# BradBoxV4.net
KiCad netlist of a schematic drawn in EAGLE
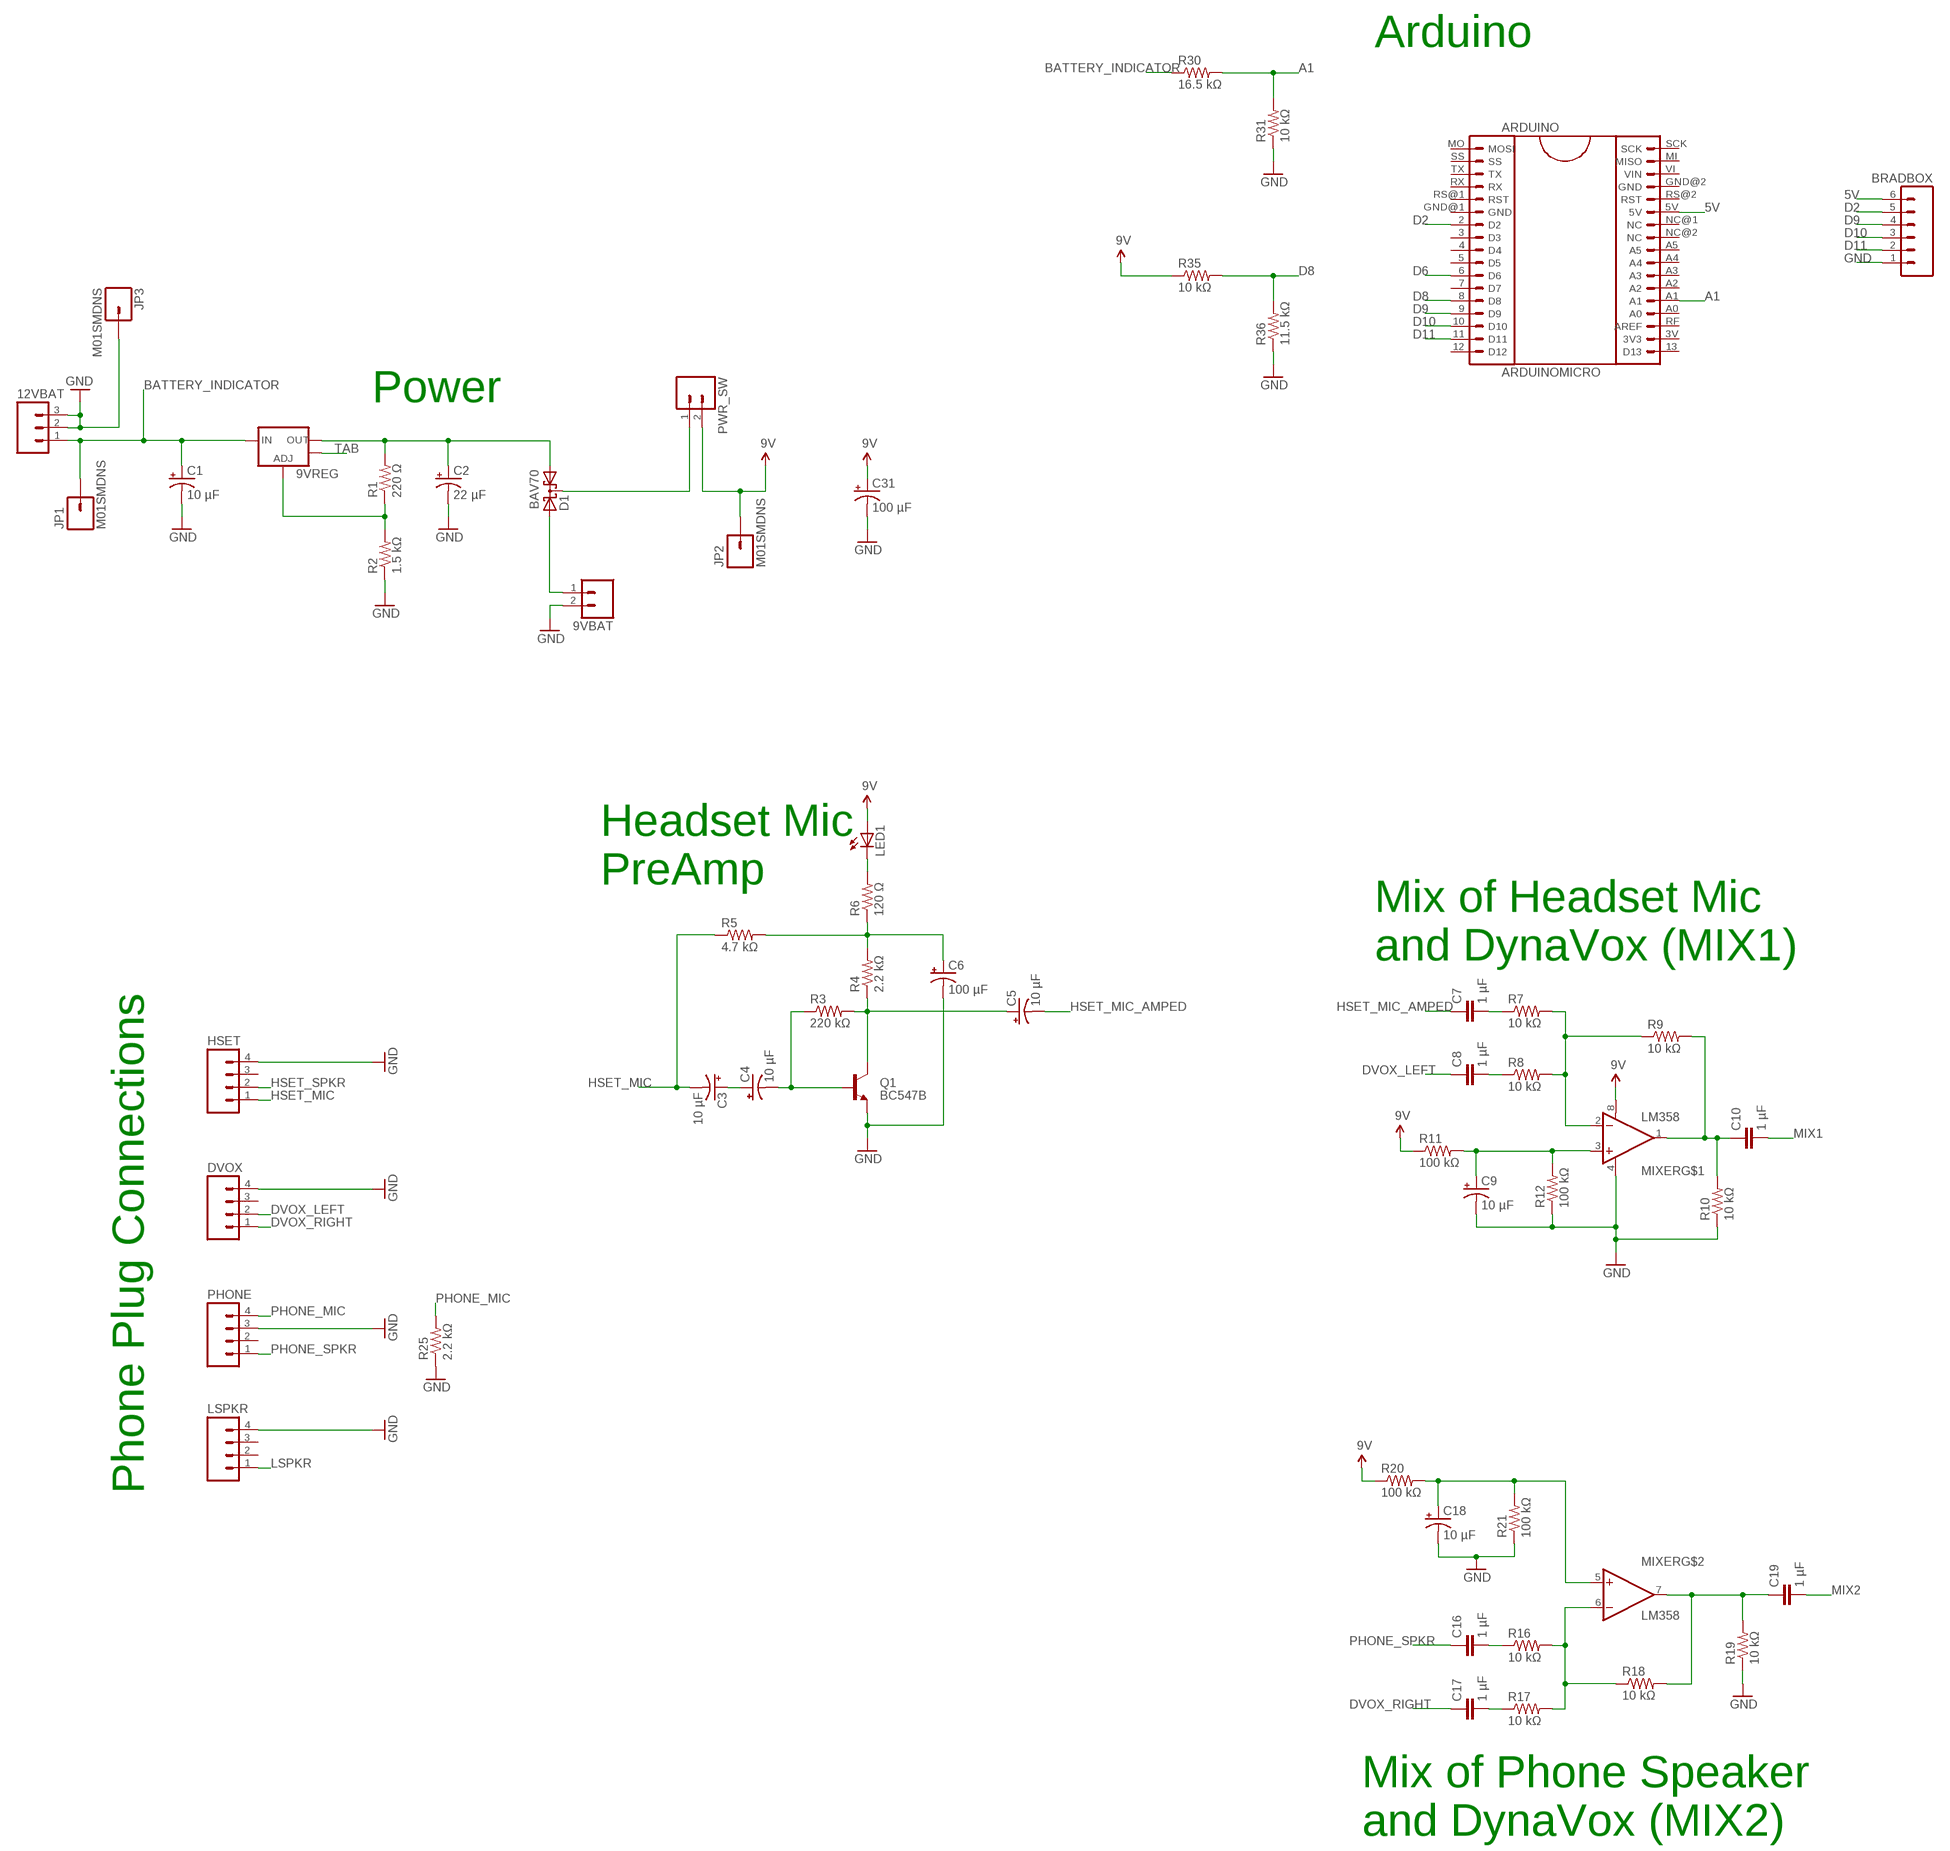
[diagram p0: schematic, sheet 1, part 1 of 2]
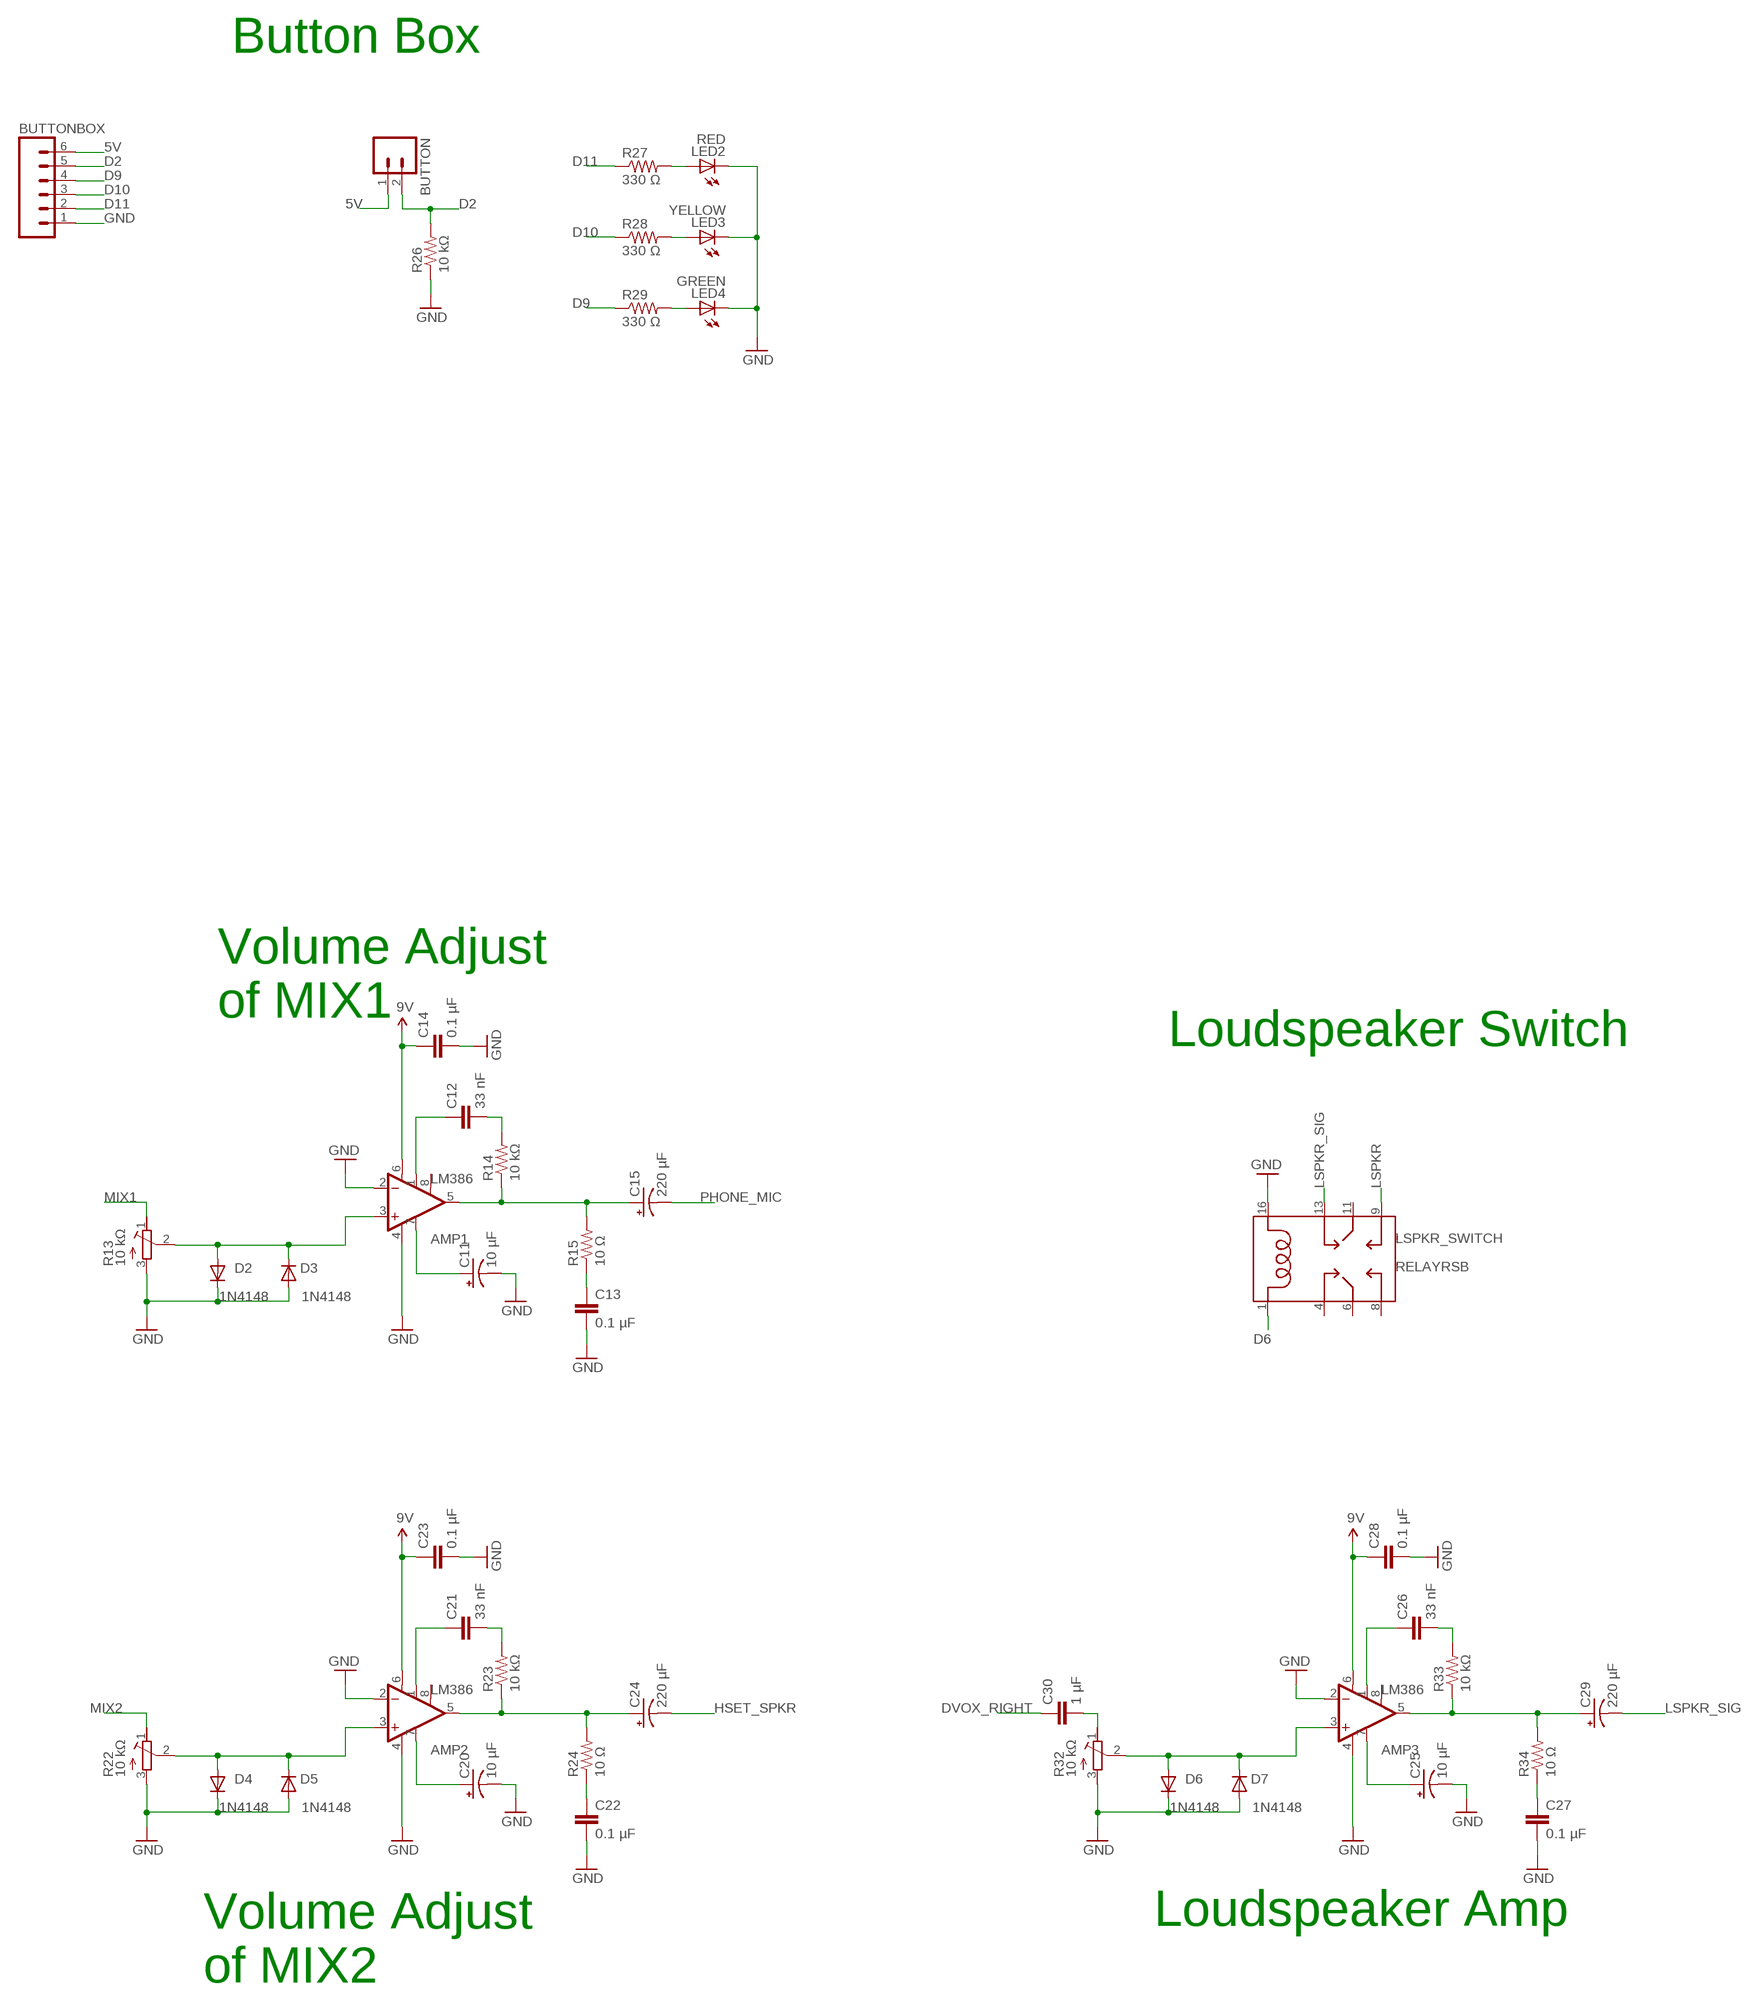
[diagram p1: schematic, sheet 1, part 2 of 2]

(export (version "E")
  (design (tool "Eeschema 10.0.6"))
  (components
    (comp (ref "9VBAT")
      (value "M02POLAR")
      (footprint "eagle-import:MOLEX-1X2")
      (libsource (lib "eagle-import") (part "M02POLAR"))
    )
    (comp (ref "9VREG")
      (value "V_REG_LM1117SOT223")
      (footprint "eagle-import:SOT223")
      (libsource (lib "eagle-import") (part "V_REG_LM1117SOT223"))
    )
    (comp (ref "12VBAT")
      (value "M03POLAR")
      (footprint "eagle-import:MOLEX-1X3")
      (libsource (lib "eagle-import") (part "M03POLAR"))
    )
    (comp (ref "AMP1")
      (value "LM386")
      (footprint "eagle-import:DIP08")
      (libsource (lib "eagle-import") (part "LM386"))
    )
    (comp (ref "AMP2")
      (value "LM386")
      (footprint "eagle-import:DIP08")
      (libsource (lib "eagle-import") (part "LM386"))
    )
    (comp (ref "AMP3")
      (value "LM386")
      (footprint "eagle-import:DIP08")
      (libsource (lib "eagle-import") (part "LM386"))
    )
    (comp (ref "ARDUINO")
      (value "ARDUINOMICRO")
      (footprint "eagle-import:ARDUINO_MICRO")
      (libsource (lib "eagle-import") (part "ARDUINOMICRO"))
    )
    (comp (ref "BRADBOX")
      (value "M06POLAR")
      (footprint "eagle-import:MOLEX-1X6")
      (libsource (lib "eagle-import") (part "M06POLAR"))
    )
    (comp (ref "BUTTON")
      (value "M02POLAR")
      (footprint "eagle-import:MOLEX-1X2")
      (libsource (lib "eagle-import") (part "M02POLAR"))
    )
    (comp (ref "BUTTONBOX")
      (value "M06POLAR")
      (footprint "eagle-import:MOLEX-1X6")
      (libsource (lib "eagle-import") (part "M06POLAR"))
    )
    (comp (ref "C1")
      (value "10 µF")
      (footprint "eagle-import:0603-CAP-POL")
      (libsource (lib "eagle-import") (part "CAP_POL0603-POL"))
    )
    (comp (ref "C2")
      (value "22 µF")
      (footprint "eagle-import:0603-CAP-POL")
      (libsource (lib "eagle-import") (part "CAP_POL0603-POL"))
    )
    (comp (ref "C3")
      (value "10 µF")
      (footprint "eagle-import:0603-CAP-POL")
      (libsource (lib "eagle-import") (part "CAP_POL0603-POL"))
    )
    (comp (ref "C4")
      (value "10 µF")
      (footprint "eagle-import:0603-CAP-POL")
      (libsource (lib "eagle-import") (part "CAP_POL0603-POL"))
    )
    (comp (ref "C5")
      (value "10 µF")
      (footprint "eagle-import:0603-CAP-POL")
      (libsource (lib "eagle-import") (part "CAP_POL0603-POL"))
    )
    (comp (ref "C6")
      (value "100 µF")
      (footprint "eagle-import:CPOL-RADIAL-100UF-100V")
      (libsource (lib "eagle-import") (part "CAP_POLPTH1"))
    )
    (comp (ref "C7")
      (value "1 µF")
      (footprint "eagle-import:0603-CAP")
      (libsource (lib "eagle-import") (part "CAP0603-CAP"))
    )
    (comp (ref "C8")
      (value "1 µF")
      (footprint "eagle-import:0603-CAP")
      (libsource (lib "eagle-import") (part "CAP0603-CAP"))
    )
    (comp (ref "C9")
      (value "10 µF")
      (footprint "eagle-import:0603-CAP-POL")
      (libsource (lib "eagle-import") (part "CAP_POL0603-POL"))
    )
    (comp (ref "C10")
      (value "1 µF")
      (footprint "eagle-import:0603-CAP")
      (libsource (lib "eagle-import") (part "CAP0603-CAP"))
    )
    (comp (ref "C11")
      (value "10 µF")
      (footprint "eagle-import:0603-CAP-POL")
      (libsource (lib "eagle-import") (part "CAP_POL0603-POL"))
    )
    (comp (ref "C12")
      (value "33 nF")
      (footprint "eagle-import:0603-CAP")
      (libsource (lib "eagle-import") (part "CAP0603-CAP"))
    )
    (comp (ref "C13")
      (value "0.1 µF")
      (footprint "eagle-import:0603-CAP")
      (libsource (lib "eagle-import") (part "CAP0603-CAP"))
    )
    (comp (ref "C14")
      (value "0.1 µF")
      (footprint "eagle-import:0603-CAP")
      (libsource (lib "eagle-import") (part "CAP0603-CAP"))
    )
    (comp (ref "C15")
      (value "220 µF")
      (footprint "eagle-import:CPOL-RADIAL-220UF-100V")
      (libsource (lib "eagle-import") (part "CAP_POLPTH4"))
    )
    (comp (ref "C16")
      (value "1 µF")
      (footprint "eagle-import:0603-CAP")
      (libsource (lib "eagle-import") (part "CAP0603-CAP"))
    )
    (comp (ref "C17")
      (value "1 µF")
      (footprint "eagle-import:0603-CAP")
      (libsource (lib "eagle-import") (part "CAP0603-CAP"))
    )
    (comp (ref "C18")
      (value "10 µF")
      (footprint "eagle-import:0603-CAP-POL")
      (libsource (lib "eagle-import") (part "CAP_POL0603-POL"))
    )
    (comp (ref "C19")
      (value "1 µF")
      (footprint "eagle-import:0603-CAP")
      (libsource (lib "eagle-import") (part "CAP0603-CAP"))
    )
    (comp (ref "C20")
      (value "10 µF")
      (footprint "eagle-import:0603-CAP-POL")
      (libsource (lib "eagle-import") (part "CAP_POL0603-POL"))
    )
    (comp (ref "C21")
      (value "33 nF")
      (footprint "eagle-import:0603-CAP")
      (libsource (lib "eagle-import") (part "CAP0603-CAP"))
    )
    (comp (ref "C22")
      (value "0.1 µF")
      (footprint "eagle-import:0603-CAP")
      (libsource (lib "eagle-import") (part "CAP0603-CAP"))
    )
    (comp (ref "C23")
      (value "0.1 µF")
      (footprint "eagle-import:0603-CAP")
      (libsource (lib "eagle-import") (part "CAP0603-CAP"))
    )
    (comp (ref "C24")
      (value "220 µF")
      (footprint "eagle-import:CPOL-RADIAL-220UF-100V")
      (libsource (lib "eagle-import") (part "CAP_POLPTH4"))
    )
    (comp (ref "C25")
      (value "10 µF")
      (footprint "eagle-import:0603-CAP-POL")
      (libsource (lib "eagle-import") (part "CAP_POL0603-POL"))
    )
    (comp (ref "C26")
      (value "33 nF")
      (footprint "eagle-import:0603-CAP")
      (libsource (lib "eagle-import") (part "CAP0603-CAP"))
    )
    (comp (ref "C27")
      (value "0.1 µF")
      (footprint "eagle-import:0603-CAP")
      (libsource (lib "eagle-import") (part "CAP0603-CAP"))
    )
    (comp (ref "C28")
      (value "0.1 µF")
      (footprint "eagle-import:0603-CAP")
      (libsource (lib "eagle-import") (part "CAP0603-CAP"))
    )
    (comp (ref "C29")
      (value "220 µF")
      (footprint "eagle-import:CPOL-RADIAL-220UF-100V")
      (libsource (lib "eagle-import") (part "CAP_POLPTH4"))
    )
    (comp (ref "C30")
      (value "1 µF")
      (footprint "eagle-import:0603-CAP")
      (libsource (lib "eagle-import") (part "CAP0603-CAP"))
    )
    (comp (ref "C31")
      (value "100 µF")
      (footprint "eagle-import:CPOL-RADIAL-100UF-100V")
      (libsource (lib "eagle-import") (part "CAP_POLPTH1"))
    )
    (comp (ref "D1")
      (value "BAV70")
      (footprint "eagle-import:SOT23")
      (libsource (lib "eagle-import") (part "BAS70-05"))
    )
    (comp (ref "D2")
      (value "1N4148")
      (footprint "eagle-import:SOD523F")
      (libsource (lib "eagle-import") (part "DIODE-SOD523F"))
    )
    (comp (ref "D3")
      (value "1N4148")
      (footprint "eagle-import:SOD523F")
      (libsource (lib "eagle-import") (part "DIODE-SOD523F"))
    )
    (comp (ref "D4")
      (value "1N4148")
      (footprint "eagle-import:SOD523F")
      (libsource (lib "eagle-import") (part "DIODE-SOD523F"))
    )
    (comp (ref "D5")
      (value "1N4148")
      (footprint "eagle-import:SOD523F")
      (libsource (lib "eagle-import") (part "DIODE-SOD523F"))
    )
    (comp (ref "D6")
      (value "1N4148")
      (footprint "eagle-import:SOD523F")
      (libsource (lib "eagle-import") (part "DIODE-SOD523F"))
    )
    (comp (ref "D7")
      (value "1N4148")
      (footprint "eagle-import:SOD523F")
      (libsource (lib "eagle-import") (part "DIODE-SOD523F"))
    )
    (comp (ref "DVOX")
      (value "M04POLAR")
      (footprint "eagle-import:MOLEX-1X4")
      (libsource (lib "eagle-import") (part "M04POLAR"))
    )
    (comp (ref "HSET")
      (value "M04POLAR")
      (footprint "eagle-import:MOLEX-1X4")
      (libsource (lib "eagle-import") (part "M04POLAR"))
    )
    (comp (ref "JP1")
      (value "M01SMDNS")
      (footprint "eagle-import:1X01NS")
      (libsource (lib "eagle-import") (part "M01SMDNS"))
    )
    (comp (ref "JP2")
      (value "M01SMDNS")
      (footprint "eagle-import:1X01NS")
      (libsource (lib "eagle-import") (part "M01SMDNS"))
    )
    (comp (ref "JP3")
      (value "M01SMDNS")
      (footprint "eagle-import:1X01NS")
      (libsource (lib "eagle-import") (part "M01SMDNS"))
    )
    (comp (ref "LED1")
      (value "LED0603")
      (footprint "eagle-import:LED-0603")
      (libsource (lib "eagle-import") (part "LED0603"))
    )
    (comp (ref "LED2")
      (value "RED")
      (footprint "eagle-import:LED5MM")
      (libsource (lib "eagle-import") (part "LED5MM"))
    )
    (comp (ref "LED3")
      (value "YELLOW")
      (footprint "eagle-import:LED5MM")
      (libsource (lib "eagle-import") (part "LED5MM"))
    )
    (comp (ref "LED4")
      (value "GREEN")
      (footprint "eagle-import:LED5MM")
      (libsource (lib "eagle-import") (part "LED5MM"))
    )
    (comp (ref "LSPKR")
      (value "M04POLAR")
      (footprint "eagle-import:MOLEX-1X4")
      (libsource (lib "eagle-import") (part "M04POLAR"))
    )
    (comp (ref "LSPKR_SWITCH")
      (value "RELAYRSB")
      (footprint "eagle-import:RELAY-RSB")
      (libsource (lib "eagle-import") (part "RELAYRSB"))
    )
    (comp (ref "MIXER")
      (value "LM358")
      (footprint "eagle-import:DIP08")
      (libsource (lib "eagle-import") (part "LM358"))
    )
    (comp (ref "PHONE")
      (value "M04POLAR")
      (footprint "eagle-import:MOLEX-1X4")
      (libsource (lib "eagle-import") (part "M04POLAR"))
    )
    (comp (ref "PWR_SW")
      (value "M02POLAR")
      (footprint "eagle-import:MOLEX-1X2")
      (libsource (lib "eagle-import") (part "M02POLAR"))
    )
    (comp (ref "Q1")
      (value "BC547B")
      (footprint "eagle-import:TO-92-AMMO")
      (libsource (lib "eagle-import") (part "TRANSISTOR_NPNTO-92-AMMO"))
    )
    (comp (ref "R1")
      (value "220 Ω")
      (footprint "eagle-import:R0603")
      (libsource (lib "eagle-import") (part "R-US_R0603"))
    )
    (comp (ref "R2")
      (value "1.5 kΩ")
      (footprint "eagle-import:R0603")
      (libsource (lib "eagle-import") (part "R-US_R0603"))
    )
    (comp (ref "R3")
      (value "220 kΩ")
      (footprint "eagle-import:R0603")
      (libsource (lib "eagle-import") (part "R-US_R0603"))
    )
    (comp (ref "R4")
      (value "2.2 kΩ")
      (footprint "eagle-import:R0603")
      (libsource (lib "eagle-import") (part "R-US_R0603"))
    )
    (comp (ref "R5")
      (value "4.7 kΩ")
      (footprint "eagle-import:R0603")
      (libsource (lib "eagle-import") (part "R-US_R0603"))
    )
    (comp (ref "R6")
      (value "120 Ω")
      (footprint "eagle-import:R0603")
      (libsource (lib "eagle-import") (part "R-US_R0603"))
    )
    (comp (ref "R7")
      (value "10 kΩ")
      (footprint "eagle-import:R0603")
      (libsource (lib "eagle-import") (part "R-US_R0603"))
    )
    (comp (ref "R8")
      (value "10 kΩ")
      (footprint "eagle-import:R0603")
      (libsource (lib "eagle-import") (part "R-US_R0603"))
    )
    (comp (ref "R9")
      (value "10 kΩ")
      (footprint "eagle-import:R0603")
      (libsource (lib "eagle-import") (part "R-US_R0603"))
    )
    (comp (ref "R10")
      (value "10 kΩ")
      (footprint "eagle-import:R0603")
      (libsource (lib "eagle-import") (part "R-US_R0603"))
    )
    (comp (ref "R11")
      (value "100 kΩ")
      (footprint "eagle-import:R0603")
      (libsource (lib "eagle-import") (part "R-US_R0603"))
    )
    (comp (ref "R12")
      (value "100 kΩ")
      (footprint "eagle-import:R0603")
      (libsource (lib "eagle-import") (part "R-US_R0603"))
    )
    (comp (ref "R13")
      (value "10 kΩ")
      (footprint "eagle-import:RTRIMT93YA")
      (libsource (lib "eagle-import") (part "R-TRIMMT93YA"))
    )
    (comp (ref "R14")
      (value "10 kΩ")
      (footprint "eagle-import:R0603")
      (libsource (lib "eagle-import") (part "R-US_R0603"))
    )
    (comp (ref "R15")
      (value "10 Ω")
      (footprint "eagle-import:R0603")
      (libsource (lib "eagle-import") (part "R-US_R0603"))
    )
    (comp (ref "R16")
      (value "10 kΩ")
      (footprint "eagle-import:R0603")
      (libsource (lib "eagle-import") (part "R-US_R0603"))
    )
    (comp (ref "R17")
      (value "10 kΩ")
      (footprint "eagle-import:R0603")
      (libsource (lib "eagle-import") (part "R-US_R0603"))
    )
    (comp (ref "R18")
      (value "10 kΩ")
      (footprint "eagle-import:R0603")
      (libsource (lib "eagle-import") (part "R-US_R0603"))
    )
    (comp (ref "R19")
      (value "10 kΩ")
      (footprint "eagle-import:R0603")
      (libsource (lib "eagle-import") (part "R-US_R0603"))
    )
    (comp (ref "R20")
      (value "100 kΩ")
      (footprint "eagle-import:R0603")
      (libsource (lib "eagle-import") (part "R-US_R0603"))
    )
    (comp (ref "R21")
      (value "100 kΩ")
      (footprint "eagle-import:R0603")
      (libsource (lib "eagle-import") (part "R-US_R0603"))
    )
    (comp (ref "R22")
      (value "10 kΩ")
      (footprint "eagle-import:RTRIMT93YA")
      (libsource (lib "eagle-import") (part "R-TRIMMT93YA"))
    )
    (comp (ref "R23")
      (value "10 kΩ")
      (footprint "eagle-import:R0603")
      (libsource (lib "eagle-import") (part "R-US_R0603"))
    )
    (comp (ref "R24")
      (value "10 Ω")
      (footprint "eagle-import:R0603")
      (libsource (lib "eagle-import") (part "R-US_R0603"))
    )
    (comp (ref "R25")
      (value "2.2 kΩ")
      (footprint "eagle-import:R0603")
      (libsource (lib "eagle-import") (part "R-US_R0603"))
    )
    (comp (ref "R26")
      (value "10 kΩ")
      (footprint "eagle-import:R0603")
      (libsource (lib "eagle-import") (part "R-US_R0603"))
    )
    (comp (ref "R27")
      (value "330 Ω")
      (footprint "eagle-import:R0603")
      (libsource (lib "eagle-import") (part "R-US_R0603"))
    )
    (comp (ref "R28")
      (value "330 Ω")
      (footprint "eagle-import:R0603")
      (libsource (lib "eagle-import") (part "R-US_R0603"))
    )
    (comp (ref "R29")
      (value "330 Ω")
      (footprint "eagle-import:R0603")
      (libsource (lib "eagle-import") (part "R-US_R0603"))
    )
    (comp (ref "R30")
      (value "16.5 kΩ")
      (footprint "eagle-import:R0603")
      (libsource (lib "eagle-import") (part "R-US_R0603"))
    )
    (comp (ref "R31")
      (value "10 kΩ")
      (footprint "eagle-import:R0603")
      (libsource (lib "eagle-import") (part "R-US_R0603"))
    )
    (comp (ref "R32")
      (value "10 kΩ")
      (footprint "eagle-import:RTRIMT93YA")
      (libsource (lib "eagle-import") (part "R-TRIMMT93YA"))
    )
    (comp (ref "R33")
      (value "10 kΩ")
      (footprint "eagle-import:R0603")
      (libsource (lib "eagle-import") (part "R-US_R0603"))
    )
    (comp (ref "R34")
      (value "10 Ω")
      (footprint "eagle-import:R0603")
      (libsource (lib "eagle-import") (part "R-US_R0603"))
    )
    (comp (ref "R35")
      (value "10 kΩ")
      (footprint "eagle-import:R0603")
      (libsource (lib "eagle-import") (part "R-US_R0603"))
    )
    (comp (ref "R36")
      (value "11.5 kΩ")
      (footprint "eagle-import:R0603")
      (libsource (lib "eagle-import") (part "R-US_R0603"))
    )
  )
  (nets
    (net (code "1") (name "/5V") (class "Default")
      (node (ref "ARDUINO") (pin "5V") (pinfunction "5V_5V") (pintype "bidirectional"))
      (node (ref "BRADBOX") (pin "6") (pinfunction "6_6") (pintype "passive"))
      (node (ref "BUTTON") (pin "1") (pinfunction "1_1") (pintype "passive"))
      (node (ref "BUTTONBOX") (pin "6") (pinfunction "6_6") (pintype "passive"))
    )
    (net (code "2") (name "/A1") (class "Default")
      (node (ref "ARDUINO") (pin "A1") (pinfunction "A1_A1") (pintype "bidirectional"))
      (node (ref "R30") (pin "2") (pinfunction "2_2") (pintype "passive"))
      (node (ref "R31") (pin "2") (pinfunction "2_2") (pintype "passive"))
    )
    (net (code "3") (name "/BATTERY_INDICATOR") (class "Default")
      (node (ref "12VBAT") (pin "1") (pinfunction "1_1") (pintype "passive"))
      (node (ref "9VREG") (pin "3") (pinfunction "IN_3") (pintype "input"))
      (node (ref "C1") (pin "1") (pinfunction "+_1") (pintype "passive"))
      (node (ref "JP1") (pin "1") (pinfunction "1_1") (pintype "passive"))
      (node (ref "R30") (pin "1") (pinfunction "1_1") (pintype "passive"))
    )
    (net (code "4") (name "/D2") (class "Default")
      (node (ref "ARDUINO") (pin "2") (pinfunction "D2_2") (pintype "bidirectional"))
      (node (ref "BRADBOX") (pin "5") (pinfunction "5_5") (pintype "passive"))
      (node (ref "BUTTON") (pin "2") (pinfunction "2_2") (pintype "passive"))
      (node (ref "BUTTONBOX") (pin "5") (pinfunction "5_5") (pintype "passive"))
      (node (ref "R26") (pin "2") (pinfunction "2_2") (pintype "passive"))
    )
    (net (code "5") (name "/D6") (class "Default")
      (node (ref "ARDUINO") (pin "6") (pinfunction "D6_6") (pintype "bidirectional"))
      (node (ref "LSPKR_SWITCH") (pin "1") (pinfunction "1_1") (pintype "bidirectional"))
    )
    (net (code "6") (name "/D8") (class "Default")
      (node (ref "ARDUINO") (pin "8") (pinfunction "D8_8") (pintype "bidirectional"))
      (node (ref "R35") (pin "2") (pinfunction "2_2") (pintype "passive"))
      (node (ref "R36") (pin "2") (pinfunction "2_2") (pintype "passive"))
    )
    (net (code "7") (name "/D9") (class "Default")
      (node (ref "ARDUINO") (pin "9") (pinfunction "D9_9") (pintype "bidirectional"))
      (node (ref "BRADBOX") (pin "4") (pinfunction "4_4") (pintype "passive"))
      (node (ref "BUTTONBOX") (pin "4") (pinfunction "4_4") (pintype "passive"))
      (node (ref "R29") (pin "1") (pinfunction "1_1") (pintype "passive"))
    )
    (net (code "8") (name "/D10") (class "Default")
      (node (ref "ARDUINO") (pin "10") (pinfunction "D10_10") (pintype "bidirectional"))
      (node (ref "BRADBOX") (pin "3") (pinfunction "3_3") (pintype "passive"))
      (node (ref "BUTTONBOX") (pin "3") (pinfunction "3_3") (pintype "passive"))
      (node (ref "R28") (pin "1") (pinfunction "1_1") (pintype "passive"))
    )
    (net (code "9") (name "/D11") (class "Default")
      (node (ref "ARDUINO") (pin "11") (pinfunction "D11_11") (pintype "bidirectional"))
      (node (ref "BRADBOX") (pin "2") (pinfunction "2_2") (pintype "passive"))
      (node (ref "BUTTONBOX") (pin "2") (pinfunction "2_2") (pintype "passive"))
      (node (ref "R27") (pin "1") (pinfunction "1_1") (pintype "passive"))
    )
    (net (code "10") (name "/DVOX_LEFT") (class "Default")
      (node (ref "C8") (pin "1") (pinfunction "1_1") (pintype "passive"))
      (node (ref "DVOX") (pin "2") (pinfunction "2_2") (pintype "passive"))
    )
    (net (code "11") (name "/DVOX_RIGHT") (class "Default")
      (node (ref "C17") (pin "1") (pinfunction "1_1") (pintype "passive"))
      (node (ref "C30") (pin "1") (pinfunction "1_1") (pintype "passive"))
      (node (ref "DVOX") (pin "1") (pinfunction "1_1") (pintype "passive"))
    )
    (net (code "12") (name "/HSET_MIC") (class "Default")
      (node (ref "C3") (pin "2") (pinfunction "-_2") (pintype "passive"))
      (node (ref "HSET") (pin "1") (pinfunction "1_1") (pintype "passive"))
      (node (ref "R5") (pin "1") (pinfunction "1_1") (pintype "passive"))
    )
    (net (code "13") (name "/HSET_MIC_AMPED") (class "Default")
      (node (ref "C5") (pin "2") (pinfunction "-_2") (pintype "passive"))
      (node (ref "C7") (pin "1") (pinfunction "1_1") (pintype "passive"))
    )
    (net (code "14") (name "/HSET_SPKR") (class "Default")
      (node (ref "C24") (pin "2") (pinfunction "-_2") (pintype "passive"))
      (node (ref "HSET") (pin "2") (pinfunction "2_2") (pintype "passive"))
    )
    (net (code "15") (name "/LSPKR") (class "Default")
      (node (ref "LSPKR") (pin "1") (pinfunction "1_1") (pintype "passive"))
      (node (ref "LSPKR_SWITCH") (pin "9") (pinfunction "9_9") (pintype "bidirectional"))
    )
    (net (code "16") (name "/LSPKR_SIG") (class "Default")
      (node (ref "C29") (pin "2") (pinfunction "-_2") (pintype "passive"))
      (node (ref "LSPKR_SWITCH") (pin "13") (pinfunction "13_13") (pintype "bidirectional"))
    )
    (net (code "17") (name "/MIX1") (class "Default")
      (node (ref "C10") (pin "2") (pinfunction "2_2") (pintype "passive"))
      (node (ref "R13") (pin "1") (pinfunction "A_1") (pintype "passive"))
    )
    (net (code "18") (name "/MIX2") (class "Default")
      (node (ref "C19") (pin "2") (pinfunction "2_2") (pintype "passive"))
      (node (ref "R22") (pin "1") (pinfunction "A_1") (pintype "passive"))
    )
    (net (code "19") (name "/PHONE_MIC") (class "Default")
      (node (ref "C15") (pin "2") (pinfunction "-_2") (pintype "passive"))
      (node (ref "PHONE") (pin "4") (pinfunction "4_4") (pintype "passive"))
      (node (ref "R25") (pin "2") (pinfunction "2_2") (pintype "passive"))
    )
    (net (code "20") (name "/PHONE_SPKR") (class "Default")
      (node (ref "C16") (pin "1") (pinfunction "1_1") (pintype "passive"))
      (node (ref "PHONE") (pin "1") (pinfunction "1_1") (pintype "passive"))
    )
    (net (code "21") (name "/TAB") (class "Default")
      (node (ref "9VREG") (pin "4") (pinfunction "OUT_4") (pintype "output"))
    )
    (net (code "22") (name "9V") (class "Default")
      (node (ref "AMP1") (pin "6") (pinfunction "V+_6") (pintype "power_in"))
      (node (ref "AMP2") (pin "6") (pinfunction "V+_6") (pintype "power_in"))
      (node (ref "AMP3") (pin "6") (pinfunction "V+_6") (pintype "power_in"))
      (node (ref "C14") (pin "1") (pinfunction "1_1") (pintype "passive"))
      (node (ref "C23") (pin "1") (pinfunction "1_1") (pintype "passive"))
      (node (ref "C28") (pin "1") (pinfunction "1_1") (pintype "passive"))
      (node (ref "C31") (pin "1") (pinfunction "+_1") (pintype "passive"))
      (node (ref "JP2") (pin "1") (pinfunction "1_1") (pintype "passive"))
      (node (ref "LED1") (pin "A") (pinfunction "A_A") (pintype "passive"))
      (node (ref "MIXER") (pin "8") (pinfunction "V+_8") (pintype "power_in"))
      (node (ref "PWR_SW") (pin "2") (pinfunction "2_2") (pintype "passive"))
      (node (ref "R11") (pin "1") (pinfunction "1_1") (pintype "passive"))
      (node (ref "R20") (pin "1") (pinfunction "1_1") (pintype "passive"))
      (node (ref "R35") (pin "1") (pinfunction "1_1") (pintype "passive"))
    )
    (net (code "23") (name "GND") (class "Default")
      (node (ref "12VBAT") (pin "2") (pinfunction "2_2") (pintype "passive"))
      (node (ref "12VBAT") (pin "3") (pinfunction "3_3") (pintype "passive"))
      (node (ref "9VBAT") (pin "2") (pinfunction "2_2") (pintype "passive"))
      (node (ref "AMP1") (pin "2") (pinfunction "-IN_2") (pintype "input"))
      (node (ref "AMP1") (pin "4") (pinfunction "V-_4") (pintype "power_in"))
      (node (ref "AMP2") (pin "2") (pinfunction "-IN_2") (pintype "input"))
      (node (ref "AMP2") (pin "4") (pinfunction "V-_4") (pintype "power_in"))
      (node (ref "AMP3") (pin "2") (pinfunction "-IN_2") (pintype "input"))
      (node (ref "AMP3") (pin "4") (pinfunction "V-_4") (pintype "power_in"))
      (node (ref "BRADBOX") (pin "1") (pinfunction "1_1") (pintype "passive"))
      (node (ref "BUTTONBOX") (pin "1") (pinfunction "1_1") (pintype "passive"))
      (node (ref "C1") (pin "2") (pinfunction "-_2") (pintype "passive"))
      (node (ref "C11") (pin "2") (pinfunction "-_2") (pintype "passive"))
      (node (ref "C13") (pin "2") (pinfunction "2_2") (pintype "passive"))
      (node (ref "C14") (pin "2") (pinfunction "2_2") (pintype "passive"))
      (node (ref "C18") (pin "2") (pinfunction "-_2") (pintype "passive"))
      (node (ref "C2") (pin "2") (pinfunction "-_2") (pintype "passive"))
      (node (ref "C20") (pin "2") (pinfunction "-_2") (pintype "passive"))
      (node (ref "C22") (pin "2") (pinfunction "2_2") (pintype "passive"))
      (node (ref "C23") (pin "2") (pinfunction "2_2") (pintype "passive"))
      (node (ref "C25") (pin "2") (pinfunction "-_2") (pintype "passive"))
      (node (ref "C27") (pin "2") (pinfunction "2_2") (pintype "passive"))
      (node (ref "C28") (pin "2") (pinfunction "2_2") (pintype "passive"))
      (node (ref "C31") (pin "2") (pinfunction "-_2") (pintype "passive"))
      (node (ref "C6") (pin "2") (pinfunction "-_2") (pintype "passive"))
      (node (ref "C9") (pin "2") (pinfunction "-_2") (pintype "passive"))
      (node (ref "D2") (pin "C") (pinfunction "C_C") (pintype "passive"))
      (node (ref "D3") (pin "A") (pinfunction "A_A") (pintype "passive"))
      (node (ref "D4") (pin "C") (pinfunction "C_C") (pintype "passive"))
      (node (ref "D5") (pin "A") (pinfunction "A_A") (pintype "passive"))
      (node (ref "D6") (pin "C") (pinfunction "C_C") (pintype "passive"))
      (node (ref "D7") (pin "A") (pinfunction "A_A") (pintype "passive"))
      (node (ref "DVOX") (pin "4") (pinfunction "4_4") (pintype "passive"))
      (node (ref "HSET") (pin "4") (pinfunction "4_4") (pintype "passive"))
      (node (ref "JP3") (pin "1") (pinfunction "1_1") (pintype "passive"))
      (node (ref "LED2") (pin "K") (pinfunction "C_K") (pintype "passive"))
      (node (ref "LED3") (pin "K") (pinfunction "C_K") (pintype "passive"))
      (node (ref "LED4") (pin "K") (pinfunction "C_K") (pintype "passive"))
      (node (ref "LSPKR") (pin "4") (pinfunction "4_4") (pintype "passive"))
      (node (ref "LSPKR_SWITCH") (pin "16") (pinfunction "16_16") (pintype "bidirectional"))
      (node (ref "MIXER") (pin "4") (pinfunction "V-_4") (pintype "power_in"))
      (node (ref "PHONE") (pin "3") (pinfunction "3_3") (pintype "passive"))
      (node (ref "Q1") (pin "1") (pinfunction "E_1") (pintype "passive"))
      (node (ref "R10") (pin "1") (pinfunction "1_1") (pintype "passive"))
      (node (ref "R12") (pin "1") (pinfunction "1_1") (pintype "passive"))
      (node (ref "R13") (pin "3") (pinfunction "E_3") (pintype "passive"))
      (node (ref "R19") (pin "1") (pinfunction "1_1") (pintype "passive"))
      (node (ref "R2") (pin "1") (pinfunction "1_1") (pintype "passive"))
      (node (ref "R21") (pin "1") (pinfunction "1_1") (pintype "passive"))
      (node (ref "R22") (pin "3") (pinfunction "E_3") (pintype "passive"))
      (node (ref "R25") (pin "1") (pinfunction "1_1") (pintype "passive"))
      (node (ref "R26") (pin "1") (pinfunction "1_1") (pintype "passive"))
      (node (ref "R31") (pin "1") (pinfunction "1_1") (pintype "passive"))
      (node (ref "R32") (pin "3") (pinfunction "E_3") (pintype "passive"))
      (node (ref "R36") (pin "1") (pinfunction "1_1") (pintype "passive"))
    )
    (net (code "24") (name "Net-(9VREG-ADJ)") (class "Default")
      (node (ref "9VREG") (pin "1") (pinfunction "ADJ_1") (pintype "input"))
      (node (ref "R1") (pin "1") (pinfunction "1_1") (pintype "passive"))
      (node (ref "R2") (pin "2") (pinfunction "2_2") (pintype "passive"))
    )
    (net (code "25") (name "Net-(AMP1-+IN)") (class "Default")
      (node (ref "AMP1") (pin "3") (pinfunction "+IN_3") (pintype "input"))
      (node (ref "D2") (pin "A") (pinfunction "A_A") (pintype "passive"))
      (node (ref "D3") (pin "C") (pinfunction "C_C") (pintype "passive"))
      (node (ref "R13") (pin "2") (pinfunction "S_2") (pintype "passive"))
    )
    (net (code "26") (name "Net-(AMP1-BP)") (class "Default")
      (node (ref "AMP1") (pin "7") (pinfunction "BP_7") (pintype "bidirectional"))
      (node (ref "C11") (pin "1") (pinfunction "+_1") (pintype "passive"))
    )
    (net (code "27") (name "Net-(AMP1-GAIN-Pad1)") (class "Default")
      (node (ref "AMP1") (pin "1") (pinfunction "GAIN_1") (pintype "bidirectional"))
      (node (ref "C12") (pin "1") (pinfunction "1_1") (pintype "passive"))
    )
    (net (code "28") (name "Net-(AMP1-OUT)") (class "Default")
      (node (ref "AMP1") (pin "5") (pinfunction "OUT_5") (pintype "output"))
      (node (ref "C15") (pin "1") (pinfunction "+_1") (pintype "passive"))
      (node (ref "R14") (pin "1") (pinfunction "1_1") (pintype "passive"))
      (node (ref "R15") (pin "2") (pinfunction "2_2") (pintype "passive"))
    )
    (net (code "29") (name "Net-(AMP2-+IN)") (class "Default")
      (node (ref "AMP2") (pin "3") (pinfunction "+IN_3") (pintype "input"))
      (node (ref "D4") (pin "A") (pinfunction "A_A") (pintype "passive"))
      (node (ref "D5") (pin "C") (pinfunction "C_C") (pintype "passive"))
      (node (ref "R22") (pin "2") (pinfunction "S_2") (pintype "passive"))
    )
    (net (code "30") (name "Net-(AMP2-BP)") (class "Default")
      (node (ref "AMP2") (pin "7") (pinfunction "BP_7") (pintype "bidirectional"))
      (node (ref "C20") (pin "1") (pinfunction "+_1") (pintype "passive"))
    )
    (net (code "31") (name "Net-(AMP2-GAIN-Pad1)") (class "Default")
      (node (ref "AMP2") (pin "1") (pinfunction "GAIN_1") (pintype "bidirectional"))
      (node (ref "C21") (pin "1") (pinfunction "1_1") (pintype "passive"))
    )
    (net (code "32") (name "Net-(AMP2-OUT)") (class "Default")
      (node (ref "AMP2") (pin "5") (pinfunction "OUT_5") (pintype "output"))
      (node (ref "C24") (pin "1") (pinfunction "+_1") (pintype "passive"))
      (node (ref "R23") (pin "1") (pinfunction "1_1") (pintype "passive"))
      (node (ref "R24") (pin "2") (pinfunction "2_2") (pintype "passive"))
    )
    (net (code "33") (name "Net-(AMP3-+IN)") (class "Default")
      (node (ref "AMP3") (pin "3") (pinfunction "+IN_3") (pintype "input"))
      (node (ref "D6") (pin "A") (pinfunction "A_A") (pintype "passive"))
      (node (ref "D7") (pin "C") (pinfunction "C_C") (pintype "passive"))
      (node (ref "R32") (pin "2") (pinfunction "S_2") (pintype "passive"))
    )
    (net (code "34") (name "Net-(AMP3-BP)") (class "Default")
      (node (ref "AMP3") (pin "7") (pinfunction "BP_7") (pintype "bidirectional"))
      (node (ref "C25") (pin "1") (pinfunction "+_1") (pintype "passive"))
    )
    (net (code "35") (name "Net-(AMP3-GAIN-Pad1)") (class "Default")
      (node (ref "AMP3") (pin "1") (pinfunction "GAIN_1") (pintype "bidirectional"))
      (node (ref "C26") (pin "1") (pinfunction "1_1") (pintype "passive"))
    )
    (net (code "36") (name "Net-(AMP3-OUT)") (class "Default")
      (node (ref "AMP3") (pin "5") (pinfunction "OUT_5") (pintype "output"))
      (node (ref "C29") (pin "1") (pinfunction "+_1") (pintype "passive"))
      (node (ref "R33") (pin "1") (pinfunction "1_1") (pintype "passive"))
      (node (ref "R34") (pin "2") (pinfunction "2_2") (pintype "passive"))
    )
    (net (code "37") (name "Net-(C2-+)") (class "Default")
      (node (ref "9VREG") (pin "2") (pinfunction "OUT_2") (pintype "output"))
      (node (ref "C2") (pin "1") (pinfunction "+_1") (pintype "passive"))
      (node (ref "D1") (pin "1") (pinfunction "A1_1") (pintype "passive"))
      (node (ref "R1") (pin "2") (pinfunction "2_2") (pintype "passive"))
    )
    (net (code "38") (name "Net-(C3-+)") (class "Default")
      (node (ref "C3") (pin "1") (pinfunction "+_1") (pintype "passive"))
      (node (ref "C4") (pin "1") (pinfunction "+_1") (pintype "passive"))
    )
    (net (code "39") (name "Net-(C4--)") (class "Default")
      (node (ref "C4") (pin "2") (pinfunction "-_2") (pintype "passive"))
      (node (ref "Q1") (pin "2") (pinfunction "B_2") (pintype "passive"))
      (node (ref "R3") (pin "1") (pinfunction "1_1") (pintype "passive"))
    )
    (net (code "40") (name "Net-(C5-+)") (class "Default")
      (node (ref "C5") (pin "1") (pinfunction "+_1") (pintype "passive"))
      (node (ref "Q1") (pin "3") (pinfunction "C_3") (pintype "passive"))
      (node (ref "R3") (pin "2") (pinfunction "2_2") (pintype "passive"))
      (node (ref "R4") (pin "1") (pinfunction "1_1") (pintype "passive"))
    )
    (net (code "41") (name "Net-(C6-+)") (class "Default")
      (node (ref "C6") (pin "1") (pinfunction "+_1") (pintype "passive"))
      (node (ref "R4") (pin "2") (pinfunction "2_2") (pintype "passive"))
      (node (ref "R5") (pin "2") (pinfunction "2_2") (pintype "passive"))
      (node (ref "R6") (pin "1") (pinfunction "1_1") (pintype "passive"))
    )
    (net (code "42") (name "Net-(C7-Pad2)") (class "Default")
      (node (ref "C7") (pin "2") (pinfunction "2_2") (pintype "passive"))
      (node (ref "R7") (pin "1") (pinfunction "1_1") (pintype "passive"))
    )
    (net (code "43") (name "Net-(C8-Pad2)") (class "Default")
      (node (ref "C8") (pin "2") (pinfunction "2_2") (pintype "passive"))
      (node (ref "R8") (pin "1") (pinfunction "1_1") (pintype "passive"))
    )
    (net (code "44") (name "Net-(C9-+)") (class "Default")
      (node (ref "C9") (pin "1") (pinfunction "+_1") (pintype "passive"))
      (node (ref "MIXER") (pin "3") (pinfunction "+IN_3") (pintype "input"))
      (node (ref "R11") (pin "2") (pinfunction "2_2") (pintype "passive"))
      (node (ref "R12") (pin "2") (pinfunction "2_2") (pintype "passive"))
    )
    (net (code "45") (name "Net-(C12-Pad2)") (class "Default")
      (node (ref "C12") (pin "2") (pinfunction "2_2") (pintype "passive"))
      (node (ref "R14") (pin "2") (pinfunction "2_2") (pintype "passive"))
    )
    (net (code "46") (name "Net-(C13-Pad1)") (class "Default")
      (node (ref "C13") (pin "1") (pinfunction "1_1") (pintype "passive"))
      (node (ref "R15") (pin "1") (pinfunction "1_1") (pintype "passive"))
    )
    (net (code "47") (name "Net-(C16-Pad2)") (class "Default")
      (node (ref "C16") (pin "2") (pinfunction "2_2") (pintype "passive"))
      (node (ref "R16") (pin "1") (pinfunction "1_1") (pintype "passive"))
    )
    (net (code "48") (name "Net-(C17-Pad2)") (class "Default")
      (node (ref "C17") (pin "2") (pinfunction "2_2") (pintype "passive"))
      (node (ref "R17") (pin "1") (pinfunction "1_1") (pintype "passive"))
    )
    (net (code "49") (name "Net-(C18-+)") (class "Default")
      (node (ref "C18") (pin "1") (pinfunction "+_1") (pintype "passive"))
      (node (ref "MIXER") (pin "5") (pinfunction "+IN_5") (pintype "input"))
      (node (ref "R20") (pin "2") (pinfunction "2_2") (pintype "passive"))
      (node (ref "R21") (pin "2") (pinfunction "2_2") (pintype "passive"))
    )
    (net (code "50") (name "Net-(C21-Pad2)") (class "Default")
      (node (ref "C21") (pin "2") (pinfunction "2_2") (pintype "passive"))
      (node (ref "R23") (pin "2") (pinfunction "2_2") (pintype "passive"))
    )
    (net (code "51") (name "Net-(C22-Pad1)") (class "Default")
      (node (ref "C22") (pin "1") (pinfunction "1_1") (pintype "passive"))
      (node (ref "R24") (pin "1") (pinfunction "1_1") (pintype "passive"))
    )
    (net (code "52") (name "Net-(C26-Pad2)") (class "Default")
      (node (ref "C26") (pin "2") (pinfunction "2_2") (pintype "passive"))
      (node (ref "R33") (pin "2") (pinfunction "2_2") (pintype "passive"))
    )
    (net (code "53") (name "Net-(C27-Pad1)") (class "Default")
      (node (ref "C27") (pin "1") (pinfunction "1_1") (pintype "passive"))
      (node (ref "R34") (pin "1") (pinfunction "1_1") (pintype "passive"))
    )
    (net (code "54") (name "Net-(D1-A2)") (class "Default")
      (node (ref "9VBAT") (pin "1") (pinfunction "1_1") (pintype "passive"))
      (node (ref "D1") (pin "2") (pinfunction "A2_2") (pintype "passive"))
    )
    (net (code "55") (name "Net-(D1-C)") (class "Default")
      (node (ref "D1") (pin "3") (pinfunction "C_3") (pintype "passive"))
      (node (ref "PWR_SW") (pin "1") (pinfunction "1_1") (pintype "passive"))
    )
    (net (code "56") (name "Net-(LED1-PadC)") (class "Default")
      (node (ref "LED1") (pin "C") (pinfunction "C_C") (pintype "passive"))
      (node (ref "R6") (pin "2") (pinfunction "2_2") (pintype "passive"))
    )
    (net (code "57") (name "Net-(LED2-PadA)") (class "Default")
      (node (ref "LED2") (pin "A") (pinfunction "A_A") (pintype "passive"))
      (node (ref "R27") (pin "2") (pinfunction "2_2") (pintype "passive"))
    )
    (net (code "58") (name "Net-(LED3-PadA)") (class "Default")
      (node (ref "LED3") (pin "A") (pinfunction "A_A") (pintype "passive"))
      (node (ref "R28") (pin "2") (pinfunction "2_2") (pintype "passive"))
    )
    (net (code "59") (name "Net-(LED4-PadA)") (class "Default")
      (node (ref "LED4") (pin "A") (pinfunction "A_A") (pintype "passive"))
      (node (ref "R29") (pin "2") (pinfunction "2_2") (pintype "passive"))
    )
    (net (code "60") (name "Net-(MIXERA--IN)") (class "Default")
      (node (ref "MIXER") (pin "2") (pinfunction "-IN_2") (pintype "input"))
      (node (ref "R7") (pin "2") (pinfunction "2_2") (pintype "passive"))
      (node (ref "R8") (pin "2") (pinfunction "2_2") (pintype "passive"))
      (node (ref "R9") (pin "1") (pinfunction "1_1") (pintype "passive"))
    )
    (net (code "61") (name "Net-(MIXERA-OUT)") (class "Default")
      (node (ref "C10") (pin "1") (pinfunction "1_1") (pintype "passive"))
      (node (ref "MIXER") (pin "1") (pinfunction "OUT_1") (pintype "output"))
      (node (ref "R10") (pin "2") (pinfunction "2_2") (pintype "passive"))
      (node (ref "R9") (pin "2") (pinfunction "2_2") (pintype "passive"))
    )
    (net (code "62") (name "Net-(MIXERB--IN)") (class "Default")
      (node (ref "MIXER") (pin "6") (pinfunction "-IN_6") (pintype "input"))
      (node (ref "R16") (pin "2") (pinfunction "2_2") (pintype "passive"))
      (node (ref "R17") (pin "2") (pinfunction "2_2") (pintype "passive"))
      (node (ref "R18") (pin "1") (pinfunction "1_1") (pintype "passive"))
    )
    (net (code "63") (name "Net-(MIXERB-OUT)") (class "Default")
      (node (ref "C19") (pin "1") (pinfunction "1_1") (pintype "passive"))
      (node (ref "MIXER") (pin "7") (pinfunction "OUT_7") (pintype "output"))
      (node (ref "R18") (pin "2") (pinfunction "2_2") (pintype "passive"))
      (node (ref "R19") (pin "2") (pinfunction "2_2") (pintype "passive"))
    )
    (net (code "64") (name "Net-(R32-A)") (class "Default")
      (node (ref "C30") (pin "2") (pinfunction "2_2") (pintype "passive"))
      (node (ref "R32") (pin "1") (pinfunction "A_1") (pintype "passive"))
    )
    (net (code "65") (name "unconnected-(AMP1-GAIN-Pad8)") (class "Default")
      (node (ref "AMP1") (pin "8") (pinfunction "GAIN_8") (pintype "bidirectional"))
    )
    (net (code "66") (name "unconnected-(AMP2-GAIN-Pad8)") (class "Default")
      (node (ref "AMP2") (pin "8") (pinfunction "GAIN_8") (pintype "bidirectional"))
    )
    (net (code "67") (name "unconnected-(AMP3-GAIN-Pad8)") (class "Default")
      (node (ref "AMP3") (pin "8") (pinfunction "GAIN_8") (pintype "bidirectional"))
    )
    (net (code "68") (name "unconnected-(ARDUINO-3V3-Pad3V)") (class "Default")
      (node (ref "ARDUINO") (pin "3V") (pinfunction "3V3_3V") (pintype "bidirectional"))
    )
    (net (code "69") (name "unconnected-(ARDUINO-AREF-PadRF)") (class "Default")
      (node (ref "ARDUINO") (pin "RF") (pinfunction "AREF_RF") (pintype "bidirectional"))
    )
    (net (code "70") (name "unconnected-(ARDUINO-D3-Pad3)") (class "Default")
      (node (ref "ARDUINO") (pin "3") (pinfunction "D3_3") (pintype "bidirectional"))
    )
    (net (code "71") (name "unconnected-(ARDUINO-D4-Pad4)") (class "Default")
      (node (ref "ARDUINO") (pin "4") (pinfunction "D4_4") (pintype "bidirectional"))
    )
    (net (code "72") (name "unconnected-(ARDUINO-D5-Pad5)") (class "Default")
      (node (ref "ARDUINO") (pin "5") (pinfunction "D5_5") (pintype "bidirectional"))
    )
    (net (code "73") (name "unconnected-(ARDUINO-D7-Pad7)") (class "Default")
      (node (ref "ARDUINO") (pin "7") (pinfunction "D7_7") (pintype "bidirectional"))
    )
    (net (code "74") (name "unconnected-(ARDUINO-D12-Pad12)") (class "Default")
      (node (ref "ARDUINO") (pin "12") (pinfunction "D12_12") (pintype "bidirectional"))
    )
    (net (code "75") (name "unconnected-(ARDUINO-D13-Pad13)") (class "Default")
      (node (ref "ARDUINO") (pin "13") (pinfunction "D13_13") (pintype "bidirectional"))
    )
    (net (code "76") (name "unconnected-(ARDUINO-GND-PadGND@1)") (class "Default")
      (node (ref "ARDUINO") (pin "GND@1") (pinfunction "GND_GND@1") (pintype "bidirectional"))
    )
    (net (code "77") (name "unconnected-(ARDUINO-GND-PadGND@2)") (class "Default")
      (node (ref "ARDUINO") (pin "GND@2") (pinfunction "GND_GND@2") (pintype "bidirectional"))
    )
    (net (code "78") (name "unconnected-(ARDUINO-MISO-PadMI)") (class "Default")
      (node (ref "ARDUINO") (pin "MI") (pinfunction "MISO_MI") (pintype "bidirectional"))
    )
    (net (code "79") (name "unconnected-(ARDUINO-MOSI-PadMO)") (class "Default")
      (node (ref "ARDUINO") (pin "MO") (pinfunction "MOSI_MO") (pintype "bidirectional"))
    )
    (net (code "80") (name "unconnected-(ARDUINO-NC-PadNC@1)") (class "Default")
      (node (ref "ARDUINO") (pin "NC@1") (pinfunction "NC_NC@1") (pintype "bidirectional"))
    )
    (net (code "81") (name "unconnected-(ARDUINO-NC-PadNC@2)") (class "Default")
      (node (ref "ARDUINO") (pin "NC@2") (pinfunction "NC_NC@2") (pintype "bidirectional"))
    )
    (net (code "82") (name "unconnected-(ARDUINO-PadA0)") (class "Default")
      (node (ref "ARDUINO") (pin "A0") (pinfunction "A0_A0") (pintype "bidirectional"))
    )
    (net (code "83") (name "unconnected-(ARDUINO-PadA2)") (class "Default")
      (node (ref "ARDUINO") (pin "A2") (pinfunction "A2_A2") (pintype "bidirectional"))
    )
    (net (code "84") (name "unconnected-(ARDUINO-PadA3)") (class "Default")
      (node (ref "ARDUINO") (pin "A3") (pinfunction "A3_A3") (pintype "bidirectional"))
    )
    (net (code "85") (name "unconnected-(ARDUINO-PadA4)") (class "Default")
      (node (ref "ARDUINO") (pin "A4") (pinfunction "A4_A4") (pintype "bidirectional"))
    )
    (net (code "86") (name "unconnected-(ARDUINO-PadA5)") (class "Default")
      (node (ref "ARDUINO") (pin "A5") (pinfunction "A5_A5") (pintype "bidirectional"))
    )
    (net (code "87") (name "unconnected-(ARDUINO-PadRX)") (class "Default")
      (node (ref "ARDUINO") (pin "RX") (pinfunction "RX_RX") (pintype "bidirectional"))
    )
    (net (code "88") (name "unconnected-(ARDUINO-PadSCK)") (class "Default")
      (node (ref "ARDUINO") (pin "SCK") (pinfunction "SCK_SCK") (pintype "bidirectional"))
    )
    (net (code "89") (name "unconnected-(ARDUINO-PadSS)") (class "Default")
      (node (ref "ARDUINO") (pin "SS") (pinfunction "SS_SS") (pintype "bidirectional"))
    )
    (net (code "90") (name "unconnected-(ARDUINO-PadTX)") (class "Default")
      (node (ref "ARDUINO") (pin "TX") (pinfunction "TX_TX") (pintype "bidirectional"))
    )
    (net (code "91") (name "unconnected-(ARDUINO-RST-PadRS@1)") (class "Default")
      (node (ref "ARDUINO") (pin "RS@1") (pinfunction "RST_RS@1") (pintype "bidirectional"))
    )
    (net (code "92") (name "unconnected-(ARDUINO-RST-PadRS@2)") (class "Default")
      (node (ref "ARDUINO") (pin "RS@2") (pinfunction "RST_RS@2") (pintype "bidirectional"))
    )
    (net (code "93") (name "unconnected-(ARDUINO-VIN-PadVI)") (class "Default")
      (node (ref "ARDUINO") (pin "VI") (pinfunction "VIN_VI") (pintype "bidirectional"))
    )
    (net (code "94") (name "unconnected-(DVOX-Pad3)") (class "Default")
      (node (ref "DVOX") (pin "3") (pinfunction "3_3") (pintype "passive"))
    )
    (net (code "95") (name "unconnected-(HSET-Pad3)") (class "Default")
      (node (ref "HSET") (pin "3") (pinfunction "3_3") (pintype "passive"))
    )
    (net (code "96") (name "unconnected-(LSPKR-Pad2)") (class "Default")
      (node (ref "LSPKR") (pin "2") (pinfunction "2_2") (pintype "passive"))
    )
    (net (code "97") (name "unconnected-(LSPKR-Pad3)") (class "Default")
      (node (ref "LSPKR") (pin "3") (pinfunction "3_3") (pintype "passive"))
    )
    (net (code "98") (name "unconnected-(LSPKR_SWITCH-Pad4)") (class "Default")
      (node (ref "LSPKR_SWITCH") (pin "4") (pinfunction "4_4") (pintype "bidirectional"))
    )
    (net (code "99") (name "unconnected-(LSPKR_SWITCH-Pad6)") (class "Default")
      (node (ref "LSPKR_SWITCH") (pin "6") (pinfunction "6_6") (pintype "bidirectional"))
    )
    (net (code "100") (name "unconnected-(LSPKR_SWITCH-Pad8)") (class "Default")
      (node (ref "LSPKR_SWITCH") (pin "8") (pinfunction "8_8") (pintype "bidirectional"))
    )
    (net (code "101") (name "unconnected-(LSPKR_SWITCH-Pad11)") (class "Default")
      (node (ref "LSPKR_SWITCH") (pin "11") (pinfunction "11_11") (pintype "bidirectional"))
    )
    (net (code "102") (name "unconnected-(PHONE-Pad2)") (class "Default")
      (node (ref "PHONE") (pin "2") (pinfunction "2_2") (pintype "passive"))
    )
  )
)
